# mainboard_v6_0_3.net
KiCad netlist of a schematic drawn in EAGLE
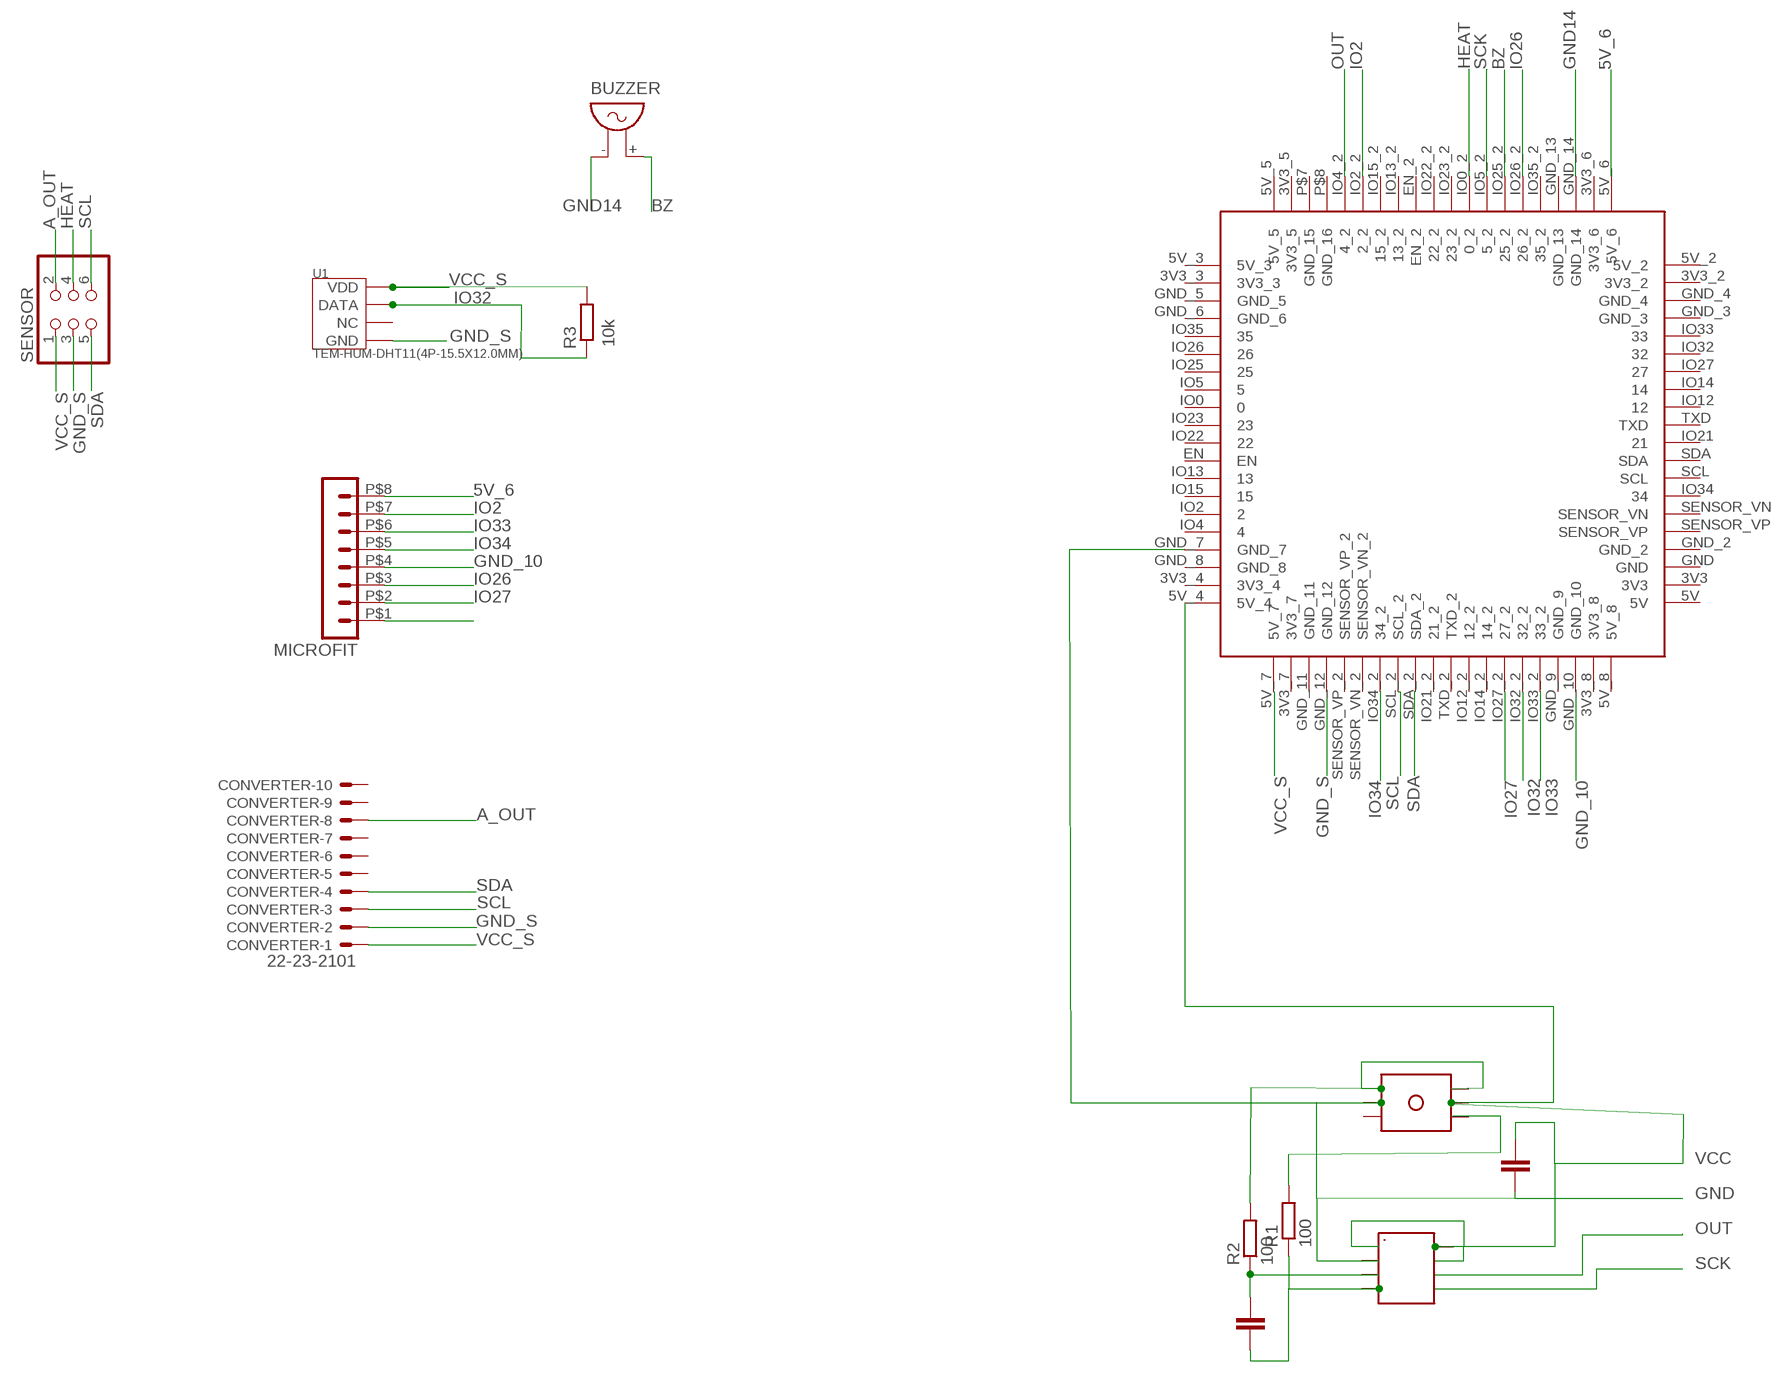
[diagram p0: schematic, sheet 1]

(export (version "E")
  (design (tool "Eeschema 10.0.6"))
  (components
    (comp (ref "BUZZER")
      (value "F/QMX")
      (footprint "eagle-import:F_QMX")
      (libsource (lib "eagle-import") (part "F/QMX"))
    )
    (comp (ref "C1")
      (value "100n")
      (footprint "eagle-import:C0805")
      (libsource (lib "eagle-import") (part "C-EUC0805"))
    )
    (comp (ref "C2")
      (value "100n")
      (footprint "eagle-import:C0805")
      (libsource (lib "eagle-import") (part "C-EUC0805"))
    )
    (comp (ref "CONVERTER")
      (value "22-23-2101")
      (footprint "eagle-import:22-23-2101")
      (fields (field (name "MF") "MOLEX"))
      (libsource (lib "eagle-import") (part "22-23-2101"))
    )
    (comp (ref "MICROFIT")
      (value "HEADER_POS8_43045-0800")
      (footprint "eagle-import:43045-0800")
      (libsource (lib "eagle-import") (part "HEADER_POS8_?43045-0800"))
    )
    (comp (ref "R1")
      (value "100")
      (footprint "eagle-import:R0805")
      (libsource (lib "eagle-import") (part "R-EU_R0805"))
    )
    (comp (ref "R2")
      (value "100")
      (footprint "eagle-import:R0805")
      (libsource (lib "eagle-import") (part "R-EU_R0805"))
    )
    (comp (ref "R3")
      (value "10k")
      (footprint "eagle-import:R0805")
      (libsource (lib "eagle-import") (part "R-EU_R0805"))
    )
    (comp (ref "SENSOR")
      (value "PINHD-2X3")
      (footprint "eagle-import:2X03")
      (libsource (lib "eagle-import") (part "PINHD-2X3"))
    )
    (comp (ref "U$1")
      (value "WT32_SC01WT32_D")
      (footprint "eagle-import:WT32_DUPLICATED")
      (libsource (lib "eagle-import") (part "WT32_SC01WT32_D"))
    )
    (comp (ref "U$2")
      (value "HX710B")
      (footprint "eagle-import:HX710B_SMD")
      (libsource (lib "eagle-import") (part "HX710B"))
    )
    (comp (ref "U$3")
      (value "PRESSUREPRESSURE_PTH")
      (footprint "eagle-import:PRESSURE_PTH")
      (libsource (lib "eagle-import") (part "PRESSUREPRESSURE_PTH"))
    )
    (comp (ref "U1")
      (value "TEM-HUM-DHT11(4P-15.5X12.0MM)")
      (footprint "eagle-import:SNR4-2.54-15.5X12.0X5.5MM")
      (fields (field (name "MF") "Panasonic Industrial Automation Sales") (field (name "MP") "DHT11"))
      (libsource (lib "eagle-import") (part "TEM-HUM-DHT11(4P-15.5X12.0MM)"))
    )
  )
  (nets
    (net (code "1") (name "/5V_6") (class "Default")
      (node (ref "MICROFIT") (pin "P$8") (pinfunction "8_P$8") (pintype "passive"))
      (node (ref "U$1") (pin "5V_6") (pinfunction "5V_6_5V_6") (pintype "bidirectional"))
    )
    (net (code "2") (name "/A_OUT") (class "Default")
      (node (ref "CONVERTER") (pin "8") (pinfunction "S_8") (pintype "passive"))
      (node (ref "SENSOR") (pin "2") (pinfunction "2_2") (pintype "passive"))
    )
    (net (code "3") (name "/BZ") (class "Default")
      (node (ref "BUZZER") (pin "+") (pinfunction "2_+") (pintype "passive"))
      (node (ref "U$1") (pin "IO25_2") (pinfunction "25_2_IO25_2") (pintype "bidirectional"))
    )
    (net (code "4") (name "/GND") (class "Default")
      (node (ref "C2") (pin "2") (pinfunction "2_2") (pintype "passive"))
      (node (ref "U$1") (pin "GND_7") (pinfunction "GND_7_GND_7") (pintype "bidirectional"))
      (node (ref "U$2") (pin "AGND") (pinfunction "AGND_AGND") (pintype "bidirectional"))
      (node (ref "U$3") (pin "2") (pinfunction "2_2") (pintype "bidirectional"))
    )
    (net (code "5") (name "/GND14") (class "Default")
      (node (ref "BUZZER") (pin "-") (pinfunction "1_-") (pintype "passive"))
      (node (ref "U$1") (pin "GND_14") (pinfunction "GND_14_GND_14") (pintype "bidirectional"))
    )
    (net (code "6") (name "/GND_10") (class "Default")
      (node (ref "MICROFIT") (pin "P$4") (pinfunction "4_P$4") (pintype "passive"))
      (node (ref "U$1") (pin "GND_10") (pinfunction "GND_10_GND_10") (pintype "bidirectional"))
    )
    (net (code "7") (name "/GND_S") (class "Default")
      (node (ref "CONVERTER") (pin "2") (pinfunction "S_2") (pintype "passive"))
      (node (ref "SENSOR") (pin "3") (pinfunction "3_3") (pintype "passive"))
      (node (ref "U$1") (pin "GND_12") (pinfunction "GND_12_GND_12") (pintype "bidirectional"))
      (node (ref "U1") (pin "4") (pinfunction "GND_4") (pintype "power_in"))
    )
    (net (code "8") (name "/HEAT") (class "Default")
      (node (ref "SENSOR") (pin "4") (pinfunction "4_4") (pintype "passive"))
      (node (ref "U$1") (pin "IO0_2") (pinfunction "0_2_IO0_2") (pintype "bidirectional"))
    )
    (net (code "9") (name "/IO2") (class "Default")
      (node (ref "MICROFIT") (pin "P$7") (pinfunction "7_P$7") (pintype "passive"))
      (node (ref "U$1") (pin "IO2_2") (pinfunction "2_2_IO2_2") (pintype "bidirectional"))
    )
    (net (code "10") (name "/IO26") (class "Default")
      (node (ref "MICROFIT") (pin "P$3") (pinfunction "3_P$3") (pintype "passive"))
      (node (ref "U$1") (pin "IO26_2") (pinfunction "26_2_IO26_2") (pintype "bidirectional"))
    )
    (net (code "11") (name "/IO27") (class "Default")
      (node (ref "MICROFIT") (pin "P$2") (pinfunction "2_P$2") (pintype "passive"))
      (node (ref "U$1") (pin "IO27_2") (pinfunction "27_2_IO27_2") (pintype "bidirectional"))
    )
    (net (code "12") (name "/IO32") (class "Default")
      (node (ref "R3") (pin "1") (pinfunction "1_1") (pintype "passive"))
      (node (ref "U$1") (pin "IO32_2") (pinfunction "32_2_IO32_2") (pintype "bidirectional"))
      (node (ref "U1") (pin "2") (pinfunction "DATA_2") (pintype "bidirectional"))
    )
    (net (code "13") (name "/IO33") (class "Default")
      (node (ref "MICROFIT") (pin "P$6") (pinfunction "6_P$6") (pintype "passive"))
      (node (ref "U$1") (pin "IO33_2") (pinfunction "33_2_IO33_2") (pintype "bidirectional"))
    )
    (net (code "14") (name "/IO34") (class "Default")
      (node (ref "MICROFIT") (pin "P$5") (pinfunction "5_P$5") (pintype "passive"))
      (node (ref "U$1") (pin "IO34_2") (pinfunction "34_2_IO34_2") (pintype "bidirectional"))
    )
    (net (code "15") (name "/N$5") (class "Default")
      (node (ref "R1") (pin "2") (pinfunction "2_2") (pintype "passive"))
      (node (ref "U$3") (pin "4") (pinfunction "4_4") (pintype "bidirectional"))
    )
    (net (code "16") (name "/N$7") (class "Default")
      (node (ref "R2") (pin "2") (pinfunction "2_2") (pintype "passive"))
      (node (ref "U$3") (pin "1") (pinfunction "1_1") (pintype "bidirectional"))
      (node (ref "U$3") (pin "6") (pinfunction "6_6") (pintype "bidirectional"))
    )
    (net (code "17") (name "/OUT") (class "Default")
      (node (ref "U$1") (pin "IO4_2") (pinfunction "4_2_IO4_2") (pintype "bidirectional"))
      (node (ref "U$2") (pin "DOUT") (pinfunction "DOUT_DOUT") (pintype "bidirectional"))
    )
    (net (code "18") (name "/SCK") (class "Default")
      (node (ref "U$1") (pin "IO5_2") (pinfunction "5_2_IO5_2") (pintype "bidirectional"))
      (node (ref "U$2") (pin "SCK") (pinfunction "SCK_SCK") (pintype "bidirectional"))
    )
    (net (code "19") (name "/SCL") (class "Default")
      (node (ref "CONVERTER") (pin "3") (pinfunction "S_3") (pintype "passive"))
      (node (ref "SENSOR") (pin "6") (pinfunction "6_6") (pintype "passive"))
      (node (ref "U$1") (pin "SCL_2") (pinfunction "SCL_2_SCL_2") (pintype "bidirectional"))
    )
    (net (code "20") (name "/SDA") (class "Default")
      (node (ref "CONVERTER") (pin "4") (pinfunction "S_4") (pintype "passive"))
      (node (ref "SENSOR") (pin "5") (pinfunction "5_5") (pintype "passive"))
      (node (ref "U$1") (pin "SDA_2") (pinfunction "SDA_2_SDA_2") (pintype "bidirectional"))
    )
    (net (code "21") (name "/VCC") (class "Default")
      (node (ref "C2") (pin "1") (pinfunction "1_1") (pintype "passive"))
      (node (ref "U$1") (pin "5V_4") (pinfunction "5V_4_5V_4") (pintype "bidirectional"))
      (node (ref "U$2") (pin "AVDD") (pinfunction "AVDD_AVDD") (pintype "bidirectional"))
      (node (ref "U$2") (pin "DVDD") (pinfunction "DVDD_DVDD") (pintype "bidirectional"))
      (node (ref "U$2") (pin "VREF") (pinfunction "VREF_VREF") (pintype "bidirectional"))
      (node (ref "U$3") (pin "5") (pinfunction "5_5") (pintype "bidirectional"))
    )
    (net (code "22") (name "/VCC_S") (class "Default")
      (node (ref "CONVERTER") (pin "1") (pinfunction "S_1") (pintype "passive"))
      (node (ref "R3") (pin "2") (pinfunction "2_2") (pintype "passive"))
      (node (ref "SENSOR") (pin "1") (pinfunction "1_1") (pintype "passive"))
      (node (ref "U$1") (pin "5V_7") (pinfunction "5V_7_5V_7") (pintype "bidirectional"))
      (node (ref "U1") (pin "1") (pinfunction "VDD_1") (pintype "power_in"))
    )
    (net (code "23") (name "Net-(C1-Pad1)") (class "Default")
      (node (ref "C1") (pin "1") (pinfunction "1_1") (pintype "passive"))
      (node (ref "R1") (pin "1") (pinfunction "1_1") (pintype "passive"))
      (node (ref "U$2") (pin "INP") (pinfunction "INP_INP") (pintype "bidirectional"))
    )
    (net (code "24") (name "Net-(C1-Pad2)") (class "Default")
      (node (ref "C1") (pin "2") (pinfunction "2_2") (pintype "passive"))
      (node (ref "R2") (pin "1") (pinfunction "1_1") (pintype "passive"))
      (node (ref "U$2") (pin "INN") (pinfunction "INN_INN") (pintype "bidirectional"))
    )
    (net (code "25") (name "unconnected-(CONVERTERB-S-Pad10)") (class "Default")
      (node (ref "CONVERTER") (pin "10") (pinfunction "S_10") (pintype "passive"))
    )
    (net (code "26") (name "unconnected-(CONVERTERF-S-Pad5)") (class "Default")
      (node (ref "CONVERTER") (pin "5") (pinfunction "S_5") (pintype "passive"))
    )
    (net (code "27") (name "unconnected-(CONVERTERG-S-Pad6)") (class "Default")
      (node (ref "CONVERTER") (pin "6") (pinfunction "S_6") (pintype "passive"))
    )
    (net (code "28") (name "unconnected-(CONVERTERH-S-Pad7)") (class "Default")
      (node (ref "CONVERTER") (pin "7") (pinfunction "S_7") (pintype "passive"))
    )
    (net (code "29") (name "unconnected-(CONVERTERJ-S-Pad9)") (class "Default")
      (node (ref "CONVERTER") (pin "9") (pinfunction "S_9") (pintype "passive"))
    )
    (net (code "30") (name "unconnected-(MICROFIT-1-PadP$1)") (class "Default")
      (node (ref "MICROFIT") (pin "P$1") (pinfunction "1_P$1") (pintype "passive"))
    )
    (net (code "31") (name "unconnected-(U$1-0-PadIO0)") (class "Default")
      (node (ref "U$1") (pin "IO0") (pinfunction "0_IO0") (pintype "bidirectional"))
    )
    (net (code "32") (name "unconnected-(U$1-2-PadIO2)") (class "Default")
      (node (ref "U$1") (pin "IO2") (pinfunction "2_IO2") (pintype "bidirectional"))
    )
    (net (code "33") (name "unconnected-(U$1-4-PadIO4)") (class "Default")
      (node (ref "U$1") (pin "IO4") (pinfunction "4_IO4") (pintype "bidirectional"))
    )
    (net (code "34") (name "unconnected-(U$1-5-PadIO5)") (class "Default")
      (node (ref "U$1") (pin "IO5") (pinfunction "5_IO5") (pintype "bidirectional"))
    )
    (net (code "35") (name "unconnected-(U$1-12-PadIO12)") (class "Default")
      (node (ref "U$1") (pin "IO12") (pinfunction "12_IO12") (pintype "bidirectional"))
    )
    (net (code "36") (name "unconnected-(U$1-12_2-PadIO12_2)") (class "Default")
      (node (ref "U$1") (pin "IO12_2") (pinfunction "12_2_IO12_2") (pintype "bidirectional"))
    )
    (net (code "37") (name "unconnected-(U$1-13-PadIO13)") (class "Default")
      (node (ref "U$1") (pin "IO13") (pinfunction "13_IO13") (pintype "bidirectional"))
    )
    (net (code "38") (name "unconnected-(U$1-13_2-PadIO13_2)") (class "Default")
      (node (ref "U$1") (pin "IO13_2") (pinfunction "13_2_IO13_2") (pintype "bidirectional"))
    )
    (net (code "39") (name "unconnected-(U$1-14-PadIO14)") (class "Default")
      (node (ref "U$1") (pin "IO14") (pinfunction "14_IO14") (pintype "bidirectional"))
    )
    (net (code "40") (name "unconnected-(U$1-14_2-PadIO14_2)") (class "Default")
      (node (ref "U$1") (pin "IO14_2") (pinfunction "14_2_IO14_2") (pintype "bidirectional"))
    )
    (net (code "41") (name "unconnected-(U$1-15-PadIO15)") (class "Default")
      (node (ref "U$1") (pin "IO15") (pinfunction "15_IO15") (pintype "bidirectional"))
    )
    (net (code "42") (name "unconnected-(U$1-15_2-PadIO15_2)") (class "Default")
      (node (ref "U$1") (pin "IO15_2") (pinfunction "15_2_IO15_2") (pintype "bidirectional"))
    )
    (net (code "43") (name "unconnected-(U$1-21-PadIO21)") (class "Default")
      (node (ref "U$1") (pin "IO21") (pinfunction "21_IO21") (pintype "bidirectional"))
    )
    (net (code "44") (name "unconnected-(U$1-21_2-PadIO21_2)") (class "Default")
      (node (ref "U$1") (pin "IO21_2") (pinfunction "21_2_IO21_2") (pintype "bidirectional"))
    )
    (net (code "45") (name "unconnected-(U$1-22-PadIO22)") (class "Default")
      (node (ref "U$1") (pin "IO22") (pinfunction "22_IO22") (pintype "bidirectional"))
    )
    (net (code "46") (name "unconnected-(U$1-22_2-PadIO22_2)") (class "Default")
      (node (ref "U$1") (pin "IO22_2") (pinfunction "22_2_IO22_2") (pintype "bidirectional"))
    )
    (net (code "47") (name "unconnected-(U$1-23-PadIO23)") (class "Default")
      (node (ref "U$1") (pin "IO23") (pinfunction "23_IO23") (pintype "bidirectional"))
    )
    (net (code "48") (name "unconnected-(U$1-23_2-PadIO23_2)") (class "Default")
      (node (ref "U$1") (pin "IO23_2") (pinfunction "23_2_IO23_2") (pintype "bidirectional"))
    )
    (net (code "49") (name "unconnected-(U$1-25-PadIO25)") (class "Default")
      (node (ref "U$1") (pin "IO25") (pinfunction "25_IO25") (pintype "bidirectional"))
    )
    (net (code "50") (name "unconnected-(U$1-26-PadIO26)") (class "Default")
      (node (ref "U$1") (pin "IO26") (pinfunction "26_IO26") (pintype "bidirectional"))
    )
    (net (code "51") (name "unconnected-(U$1-27-PadIO27)") (class "Default")
      (node (ref "U$1") (pin "IO27") (pinfunction "27_IO27") (pintype "bidirectional"))
    )
    (net (code "52") (name "unconnected-(U$1-32-PadIO32)") (class "Default")
      (node (ref "U$1") (pin "IO32") (pinfunction "32_IO32") (pintype "bidirectional"))
    )
    (net (code "53") (name "unconnected-(U$1-33-PadIO33)") (class "Default")
      (node (ref "U$1") (pin "IO33") (pinfunction "33_IO33") (pintype "bidirectional"))
    )
    (net (code "54") (name "unconnected-(U$1-34-PadIO34)") (class "Default")
      (node (ref "U$1") (pin "IO34") (pinfunction "34_IO34") (pintype "bidirectional"))
    )
    (net (code "55") (name "unconnected-(U$1-35-PadIO35)") (class "Default")
      (node (ref "U$1") (pin "IO35") (pinfunction "35_IO35") (pintype "bidirectional"))
    )
    (net (code "56") (name "unconnected-(U$1-35_2-PadIO35_2)") (class "Default")
      (node (ref "U$1") (pin "IO35_2") (pinfunction "35_2_IO35_2") (pintype "bidirectional"))
    )
    (net (code "57") (name "unconnected-(U$1-GND_15-PadP$7)") (class "Default")
      (node (ref "U$1") (pin "P$7") (pinfunction "GND_15_P$7") (pintype "bidirectional"))
    )
    (net (code "58") (name "unconnected-(U$1-GND_16-PadP$8)") (class "Default")
      (node (ref "U$1") (pin "P$8") (pinfunction "GND_16_P$8") (pintype "bidirectional"))
    )
    (net (code "59") (name "unconnected-(U$1-Pad3V3)") (class "Default")
      (node (ref "U$1") (pin "3V3") (pinfunction "3V3_3V3") (pintype "bidirectional"))
    )
    (net (code "60") (name "unconnected-(U$1-Pad3V3_2)") (class "Default")
      (node (ref "U$1") (pin "3V3_2") (pinfunction "3V3_2_3V3_2") (pintype "bidirectional"))
    )
    (net (code "61") (name "unconnected-(U$1-Pad3V3_3)") (class "Default")
      (node (ref "U$1") (pin "3V3_3") (pinfunction "3V3_3_3V3_3") (pintype "bidirectional"))
    )
    (net (code "62") (name "unconnected-(U$1-Pad3V3_4)") (class "Default")
      (node (ref "U$1") (pin "3V3_4") (pinfunction "3V3_4_3V3_4") (pintype "bidirectional"))
    )
    (net (code "63") (name "unconnected-(U$1-Pad3V3_5)") (class "Default")
      (node (ref "U$1") (pin "3V3_5") (pinfunction "3V3_5_3V3_5") (pintype "bidirectional"))
    )
    (net (code "64") (name "unconnected-(U$1-Pad3V3_6)") (class "Default")
      (node (ref "U$1") (pin "3V3_6") (pinfunction "3V3_6_3V3_6") (pintype "bidirectional"))
    )
    (net (code "65") (name "unconnected-(U$1-Pad3V3_7)") (class "Default")
      (node (ref "U$1") (pin "3V3_7") (pinfunction "3V3_7_3V3_7") (pintype "bidirectional"))
    )
    (net (code "66") (name "unconnected-(U$1-Pad3V3_8)") (class "Default")
      (node (ref "U$1") (pin "3V3_8") (pinfunction "3V3_8_3V3_8") (pintype "bidirectional"))
    )
    (net (code "67") (name "unconnected-(U$1-Pad5V)") (class "Default")
      (node (ref "U$1") (pin "5V") (pinfunction "5V_5V") (pintype "bidirectional"))
    )
    (net (code "68") (name "unconnected-(U$1-Pad5V_2)") (class "Default")
      (node (ref "U$1") (pin "5V_2") (pinfunction "5V_2_5V_2") (pintype "bidirectional"))
    )
    (net (code "69") (name "unconnected-(U$1-Pad5V_3)") (class "Default")
      (node (ref "U$1") (pin "5V_3") (pinfunction "5V_3_5V_3") (pintype "bidirectional"))
    )
    (net (code "70") (name "unconnected-(U$1-Pad5V_5)") (class "Default")
      (node (ref "U$1") (pin "5V_5") (pinfunction "5V_5_5V_5") (pintype "bidirectional"))
    )
    (net (code "71") (name "unconnected-(U$1-Pad5V_8)") (class "Default")
      (node (ref "U$1") (pin "5V_8") (pinfunction "5V_8_5V_8") (pintype "bidirectional"))
    )
    (net (code "72") (name "unconnected-(U$1-PadEN)") (class "Default")
      (node (ref "U$1") (pin "EN") (pinfunction "EN_EN") (pintype "bidirectional"))
    )
    (net (code "73") (name "unconnected-(U$1-PadEN_2)") (class "Default")
      (node (ref "U$1") (pin "EN_2") (pinfunction "EN_2_EN_2") (pintype "bidirectional"))
    )
    (net (code "74") (name "unconnected-(U$1-PadGND)") (class "Default")
      (node (ref "U$1") (pin "GND") (pinfunction "GND_GND") (pintype "bidirectional"))
    )
    (net (code "75") (name "unconnected-(U$1-PadGND_2)") (class "Default")
      (node (ref "U$1") (pin "GND_2") (pinfunction "GND_2_GND_2") (pintype "bidirectional"))
    )
    (net (code "76") (name "unconnected-(U$1-PadGND_3)") (class "Default")
      (node (ref "U$1") (pin "GND_3") (pinfunction "GND_3_GND_3") (pintype "bidirectional"))
    )
    (net (code "77") (name "unconnected-(U$1-PadGND_4)") (class "Default")
      (node (ref "U$1") (pin "GND_4") (pinfunction "GND_4_GND_4") (pintype "bidirectional"))
    )
    (net (code "78") (name "unconnected-(U$1-PadGND_5)") (class "Default")
      (node (ref "U$1") (pin "GND_5") (pinfunction "GND_5_GND_5") (pintype "bidirectional"))
    )
    (net (code "79") (name "unconnected-(U$1-PadGND_6)") (class "Default")
      (node (ref "U$1") (pin "GND_6") (pinfunction "GND_6_GND_6") (pintype "bidirectional"))
    )
    (net (code "80") (name "unconnected-(U$1-PadGND_8)") (class "Default")
      (node (ref "U$1") (pin "GND_8") (pinfunction "GND_8_GND_8") (pintype "bidirectional"))
    )
    (net (code "81") (name "unconnected-(U$1-PadGND_9)") (class "Default")
      (node (ref "U$1") (pin "GND_9") (pinfunction "GND_9_GND_9") (pintype "bidirectional"))
    )
    (net (code "82") (name "unconnected-(U$1-PadGND_11)") (class "Default")
      (node (ref "U$1") (pin "GND_11") (pinfunction "GND_11_GND_11") (pintype "bidirectional"))
    )
    (net (code "83") (name "unconnected-(U$1-PadGND_13)") (class "Default")
      (node (ref "U$1") (pin "GND_13") (pinfunction "GND_13_GND_13") (pintype "bidirectional"))
    )
    (net (code "84") (name "unconnected-(U$1-PadSCL)") (class "Default")
      (node (ref "U$1") (pin "SCL") (pinfunction "SCL_SCL") (pintype "bidirectional"))
    )
    (net (code "85") (name "unconnected-(U$1-PadSDA)") (class "Default")
      (node (ref "U$1") (pin "SDA") (pinfunction "SDA_SDA") (pintype "bidirectional"))
    )
    (net (code "86") (name "unconnected-(U$1-PadSENSOR_VN)") (class "Default")
      (node (ref "U$1") (pin "SENSOR_VN") (pinfunction "SENSOR_VN_SENSOR_VN") (pintype "bidirectional"))
    )
    (net (code "87") (name "unconnected-(U$1-PadSENSOR_VN_2)") (class "Default")
      (node (ref "U$1") (pin "SENSOR_VN_2") (pinfunction "SENSOR_VN_2_SENSOR_VN_2") (pintype "bidirectional"))
    )
    (net (code "88") (name "unconnected-(U$1-PadSENSOR_VP)") (class "Default")
      (node (ref "U$1") (pin "SENSOR_VP") (pinfunction "SENSOR_VP_SENSOR_VP") (pintype "bidirectional"))
    )
    (net (code "89") (name "unconnected-(U$1-PadSENSOR_VP_2)") (class "Default")
      (node (ref "U$1") (pin "SENSOR_VP_2") (pinfunction "SENSOR_VP_2_SENSOR_VP_2") (pintype "bidirectional"))
    )
    (net (code "90") (name "unconnected-(U$1-PadTXD)") (class "Default")
      (node (ref "U$1") (pin "TXD") (pinfunction "TXD_TXD") (pintype "bidirectional"))
    )
    (net (code "91") (name "unconnected-(U$1-PadTXD_2)") (class "Default")
      (node (ref "U$1") (pin "TXD_2") (pinfunction "TXD_2_TXD_2") (pintype "bidirectional"))
    )
    (net (code "92") (name "unconnected-(U$3-Pad3)") (class "Default")
      (node (ref "U$3") (pin "3") (pinfunction "3_3") (pintype "bidirectional"))
    )
    (net (code "93") (name "unconnected-(U1-NC-Pad3)") (class "Default")
      (node (ref "U1") (pin "3") (pinfunction "NC_3") (pintype "no_connect"))
    )
  )
)
